# Coincidence.net
KiCad netlist of a schematic drawn in Altium Designer
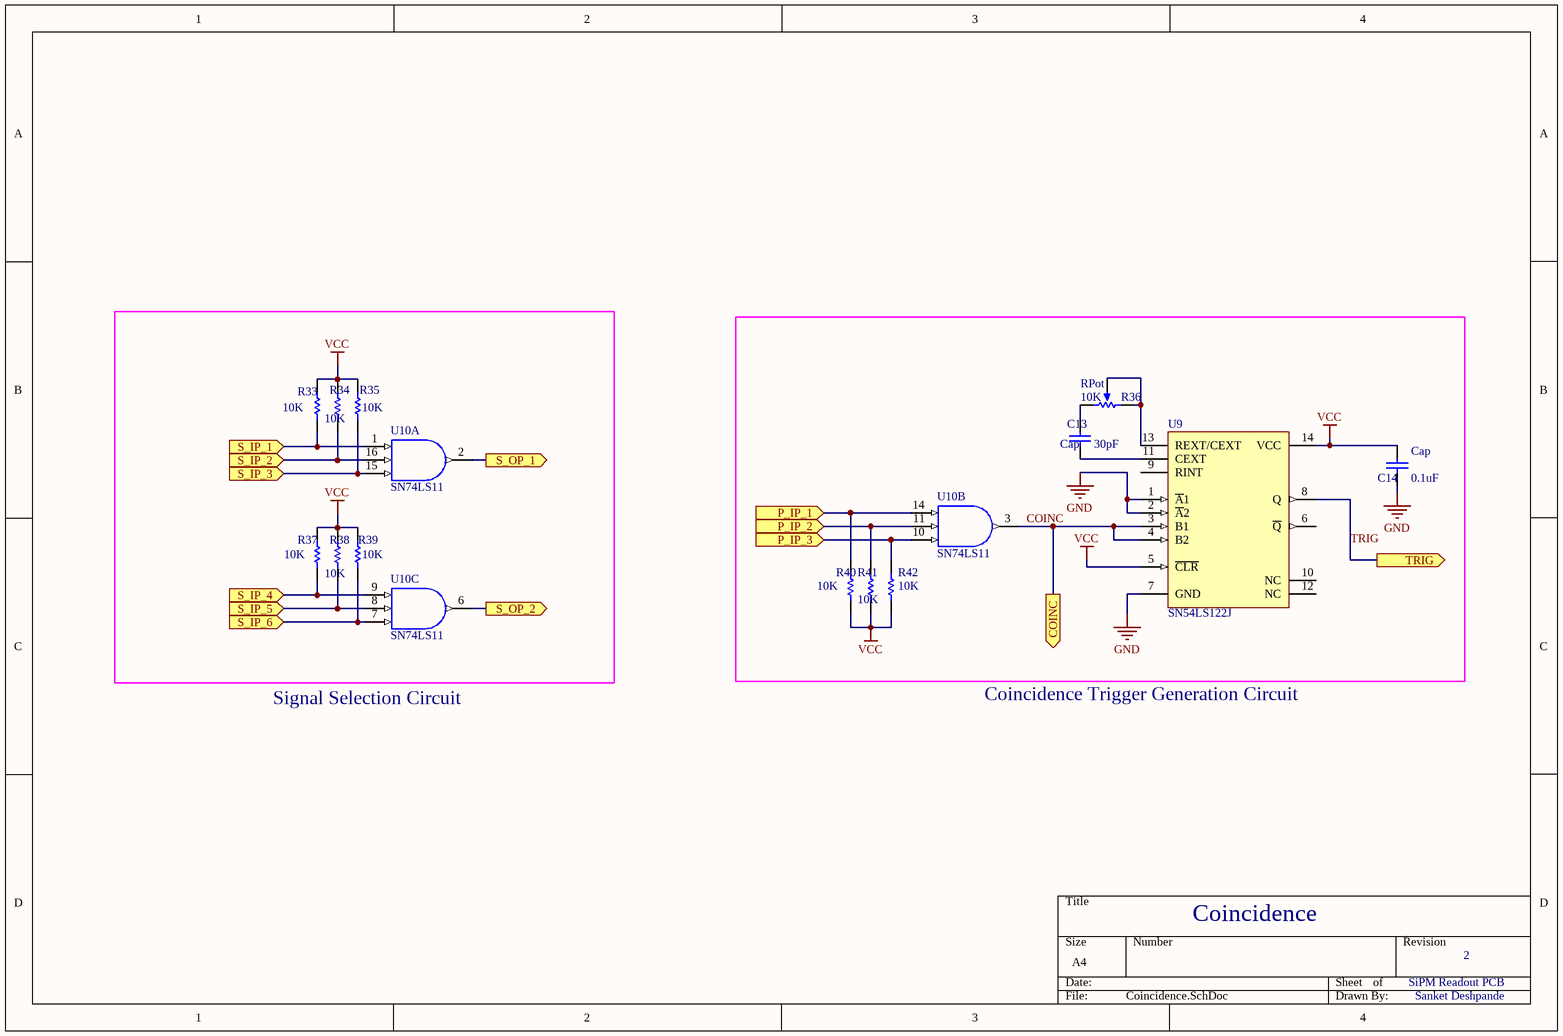
[diagram p0: Coincidence.SchDoc]

(export (version "E")
  (design (tool "Eeschema 10.0.6"))
  (components
    (comp (ref "C13")
      (value "Cap")
      (footprint "RAD-0.3")
      (description "Capacitor")
      (fields (field (name "ALTIUM_VALUE") "30pF") (field (name "PUBLISHER") "Altium Limited"))
      (libsource (lib "Miscellaneous Devices") (part "Cap"))
    )
    (comp (ref "C14")
      (value "Cap")
      (footprint "RAD-0.3")
      (description "Capacitor")
      (fields (field (name "ALTIUM_VALUE") "0.1uF") (field (name "PUBLISHER") "Altium Limited"))
      (libsource (lib "Miscellaneous Devices") (part "Cap"))
    )
    (comp (ref "R33")
      (value "10K")
      (footprint "AXIAL-0.3")
      (description "Resistor")
      (fields (field (name "Comment") "Res1") (field (name "PUBLISHER") "Altium Limited"))
      (libsource (lib "Miscellaneous Devices") (part "Res1"))
    )
    (comp (ref "R34")
      (value "10K")
      (footprint "AXIAL-0.3")
      (description "Resistor")
      (fields (field (name "Comment") "Res1") (field (name "PUBLISHER") "Altium Limited"))
      (libsource (lib "Miscellaneous Devices") (part "Res1"))
    )
    (comp (ref "R35")
      (value "10K")
      (footprint "AXIAL-0.3")
      (description "Resistor")
      (fields (field (name "Comment") "Res1") (field (name "PUBLISHER") "Altium Limited"))
      (libsource (lib "Miscellaneous Devices") (part "Res1"))
    )
    (comp (ref "R36")
      (value "RPot")
      (footprint "VR5")
      (description "Potentiometer")
      (fields (field (name "ALTIUM_VALUE") "10K") (field (name "PUBLISHER") "Altium Limited"))
      (libsource (lib "Miscellaneous Devices") (part "RPot"))
    )
    (comp (ref "R37")
      (value "10K")
      (footprint "AXIAL-0.3")
      (description "Resistor")
      (fields (field (name "Comment") "Res1") (field (name "PUBLISHER") "Altium Limited"))
      (libsource (lib "Miscellaneous Devices") (part "Res1"))
    )
    (comp (ref "R38")
      (value "10K")
      (footprint "AXIAL-0.3")
      (description "Resistor")
      (fields (field (name "Comment") "Res1") (field (name "PUBLISHER") "Altium Limited"))
      (libsource (lib "Miscellaneous Devices") (part "Res1"))
    )
    (comp (ref "R39")
      (value "10K")
      (footprint "AXIAL-0.3")
      (description "Resistor")
      (fields (field (name "Comment") "Res1") (field (name "PUBLISHER") "Altium Limited"))
      (libsource (lib "Miscellaneous Devices") (part "Res1"))
    )
    (comp (ref "R40")
      (value "10K")
      (footprint "AXIAL-0.3")
      (description "Resistor")
      (fields (field (name "Comment") "Res1") (field (name "PUBLISHER") "Altium Limited"))
      (libsource (lib "Miscellaneous Devices") (part "Res1"))
    )
    (comp (ref "R41")
      (value "10K")
      (footprint "AXIAL-0.3")
      (description "Resistor")
      (fields (field (name "Comment") "Res1") (field (name "PUBLISHER") "Altium Limited"))
      (libsource (lib "Miscellaneous Devices") (part "Res1"))
    )
    (comp (ref "R42")
      (value "10K")
      (footprint "AXIAL-0.3")
      (description "Resistor")
      (fields (field (name "Comment") "Res1") (field (name "PUBLISHER") "Altium Limited"))
      (libsource (lib "Miscellaneous Devices") (part "Res1"))
    )
    (comp (ref "U9")
      (value "SN54LS122J")
      (footprint "J014")
      (description "Retriggerable Monostable Multivibrator")
      (fields (field (name "PUBLISHER") "Altium Limited"))
      (libsource (lib "TI Logic Multivibrator") (part "SN54LS122J"))
    )
    (comp (ref "U10")
      (value "SN74LS11")
      (footprint "J016")
      (description "Triple 3-Input Positive-AND Gate")
      (fields (field (name "PUBLISHER") "Altium Limited"))
      (libsource (lib "TI Logic Gate 1") (part "54AC11011J"))
    )
  )
  (nets
    (net (code "1") (name "/COINC") (class "Default")
      (node (ref "U10") (pin "3") (pinfunction "Y_3") (pintype "output"))
      (node (ref "U9") (pin "3") (pinfunction "B1_3") (pintype "input"))
      (node (ref "U9") (pin "4") (pinfunction "B2_4") (pintype "input"))
    )
    (net (code "2") (name "/P_IP_1") (class "Default")
      (node (ref "R40") (pin "2") (pinfunction "2_2") (pintype "passive"))
      (node (ref "U10") (pin "14") (pinfunction "A_14") (pintype "input"))
    )
    (net (code "3") (name "/P_IP_2") (class "Default")
      (node (ref "R41") (pin "2") (pinfunction "2_2") (pintype "passive"))
      (node (ref "U10") (pin "11") (pinfunction "B_11") (pintype "input"))
    )
    (net (code "4") (name "/P_IP_3") (class "Default")
      (node (ref "R42") (pin "2") (pinfunction "2_2") (pintype "passive"))
      (node (ref "U10") (pin "10") (pinfunction "C_10") (pintype "input"))
    )
    (net (code "5") (name "/S_IP_1") (class "Default")
      (node (ref "R33") (pin "2") (pinfunction "2_2") (pintype "passive"))
      (node (ref "U10") (pin "1") (pinfunction "A_1") (pintype "input"))
    )
    (net (code "6") (name "/S_IP_2") (class "Default")
      (node (ref "R34") (pin "2") (pinfunction "2_2") (pintype "passive"))
      (node (ref "U10") (pin "16") (pinfunction "B_16") (pintype "input"))
    )
    (net (code "7") (name "/S_IP_3") (class "Default")
      (node (ref "R35") (pin "2") (pinfunction "2_2") (pintype "passive"))
      (node (ref "U10") (pin "15") (pinfunction "C_15") (pintype "input"))
    )
    (net (code "8") (name "/S_IP_4") (class "Default")
      (node (ref "R37") (pin "2") (pinfunction "2_2") (pintype "passive"))
      (node (ref "U10") (pin "9") (pinfunction "A_9") (pintype "input"))
    )
    (net (code "9") (name "/S_IP_5") (class "Default")
      (node (ref "R38") (pin "2") (pinfunction "2_2") (pintype "passive"))
      (node (ref "U10") (pin "8") (pinfunction "B_8") (pintype "input"))
    )
    (net (code "10") (name "/S_IP_6") (class "Default")
      (node (ref "R39") (pin "2") (pinfunction "2_2") (pintype "passive"))
      (node (ref "U10") (pin "7") (pinfunction "C_7") (pintype "input"))
    )
    (net (code "11") (name "/S_OP_1") (class "Default")
      (node (ref "U10") (pin "2") (pinfunction "Y_2") (pintype "output"))
    )
    (net (code "12") (name "/S_OP_2") (class "Default")
      (node (ref "U10") (pin "6") (pinfunction "Y_6") (pintype "output"))
    )
    (net (code "13") (name "/TRIG") (class "Default")
      (node (ref "U9") (pin "8") (pinfunction "Q_8") (pintype "output"))
    )
    (net (code "14") (name "GND") (class "Default")
      (node (ref "C14") (pin "1") (pinfunction "1_1") (pintype "passive"))
      (node (ref "U10") (pin "4") (pinfunction "GND_4") (pintype "power_in"))
      (node (ref "U10") (pin "5") (pinfunction "GND_5") (pintype "power_in"))
      (node (ref "U9") (pin "1") (pinfunction "~{A}1_1") (pintype "input"))
      (node (ref "U9") (pin "2") (pinfunction "~{A}2_2") (pintype "input"))
      (node (ref "U9") (pin "7") (pinfunction "GND_7") (pintype "power_in"))
    )
    (net (code "15") (name "Net-(R36-BOT)") (class "Default")
      (node (ref "C13") (pin "2") (pinfunction "2_2") (pintype "passive"))
      (node (ref "R36") (pin "2") (pinfunction "BOT_2") (pintype "passive"))
    )
    (net (code "16") (name "Net-(R36-TAP)") (class "Default")
      (node (ref "R36") (pin "1") (pinfunction "TOP_1") (pintype "passive"))
      (node (ref "R36") (pin "3") (pinfunction "TAP_3") (pintype "passive"))
      (node (ref "U9") (pin "13") (pinfunction "REXT/CEXT_13") (pintype "passive"))
    )
    (net (code "17") (name "Net-(U9-CEXT)") (class "Default")
      (node (ref "C13") (pin "1") (pinfunction "1_1") (pintype "passive"))
      (node (ref "U9") (pin "11") (pinfunction "CEXT_11") (pintype "passive"))
    )
    (net (code "18") (name "VCC") (class "Default")
      (node (ref "C14") (pin "2") (pinfunction "2_2") (pintype "passive"))
      (node (ref "R33") (pin "1") (pinfunction "1_1") (pintype "passive"))
      (node (ref "R34") (pin "1") (pinfunction "1_1") (pintype "passive"))
      (node (ref "R35") (pin "1") (pinfunction "1_1") (pintype "passive"))
      (node (ref "R37") (pin "1") (pinfunction "1_1") (pintype "passive"))
      (node (ref "R38") (pin "1") (pinfunction "1_1") (pintype "passive"))
      (node (ref "R39") (pin "1") (pinfunction "1_1") (pintype "passive"))
      (node (ref "R40") (pin "1") (pinfunction "1_1") (pintype "passive"))
      (node (ref "R41") (pin "1") (pinfunction "1_1") (pintype "passive"))
      (node (ref "R42") (pin "1") (pinfunction "1_1") (pintype "passive"))
      (node (ref "U10") (pin "12") (pinfunction "VCC_12") (pintype "power_in"))
      (node (ref "U10") (pin "13") (pinfunction "VCC_13") (pintype "power_in"))
      (node (ref "U9") (pin "14") (pinfunction "VCC_14") (pintype "power_in"))
      (node (ref "U9") (pin "5") (pinfunction "~{CLR}_5") (pintype "input"))
    )
    (net (code "19") (name "unconnected-(U9-NC-Pad10)") (class "Default")
      (node (ref "U9") (pin "10") (pinfunction "NC_10") (pintype "passive"))
    )
    (net (code "20") (name "unconnected-(U9-NC-Pad12)") (class "Default")
      (node (ref "U9") (pin "12") (pinfunction "NC_12") (pintype "passive"))
    )
    (net (code "21") (name "unconnected-(U9-RINT-Pad9)") (class "Default")
      (node (ref "U9") (pin "9") (pinfunction "RINT_9") (pintype "passive"))
    )
    (net (code "22") (name "unconnected-(U9-~{Q}-Pad6)") (class "Default")
      (node (ref "U9") (pin "6") (pinfunction "~{Q}_6") (pintype "output"))
    )
  )
)
